# out8.net
KiCad netlist of a schematic drawn in EAGLE
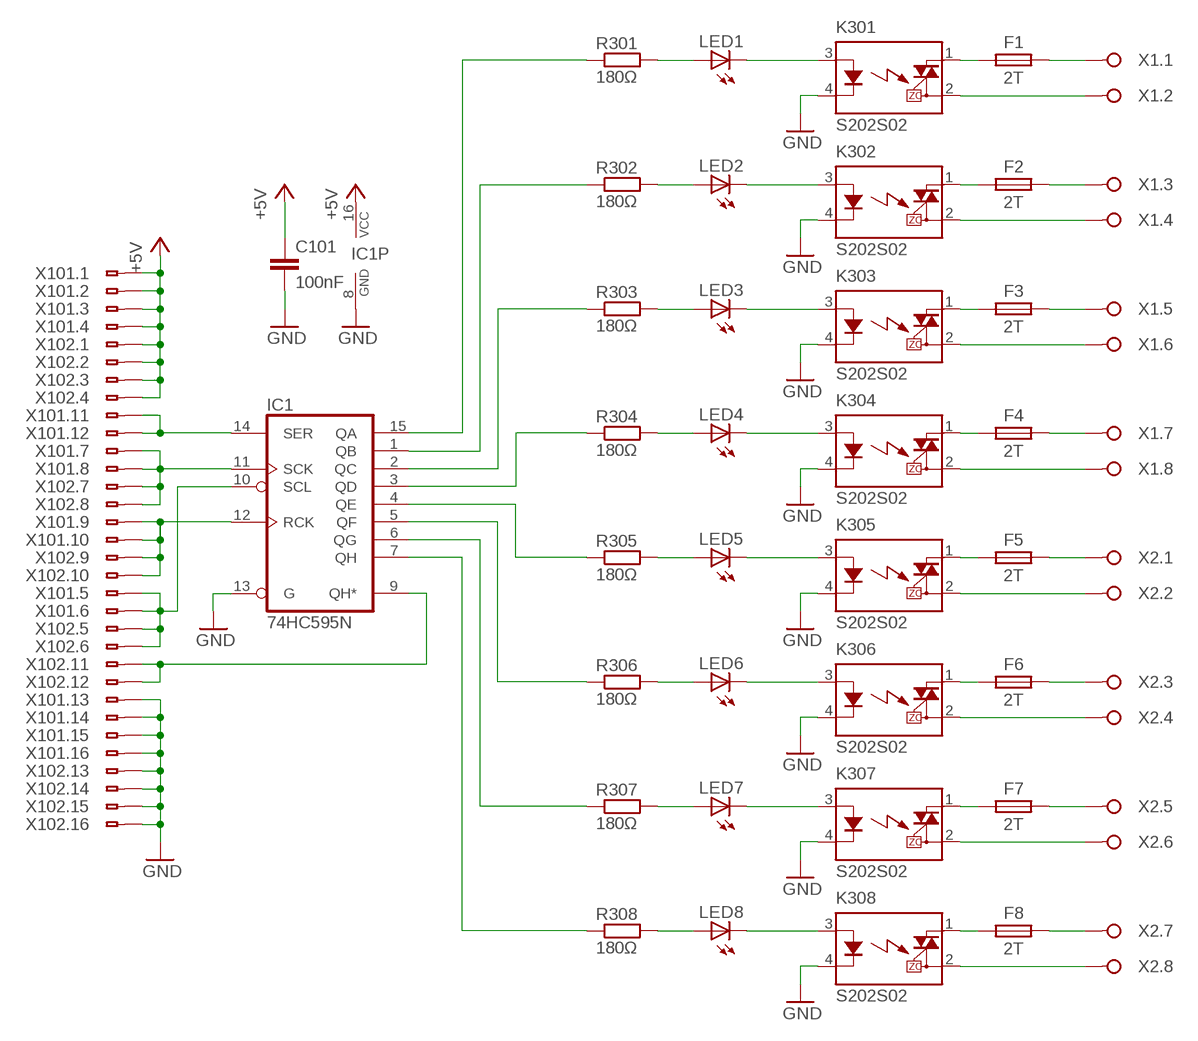
[diagram p0: schematic, sheet 1]

(export (version "E")
  (design (tool "Eeschema 10.0.6"))
  (components
    (comp (ref "C101")
      (value "100nF")
      (footprint "eagle-import:C025-025X050")
      (libsource (lib "eagle-import") (part "C_025-025X050"))
    )
    (comp (ref "F1")
      (value "2T")
      (footprint "eagle-import:TR5")
      (libsource (lib "eagle-import") (part "TR5"))
    )
    (comp (ref "F2")
      (value "2T")
      (footprint "eagle-import:TR5")
      (libsource (lib "eagle-import") (part "TR5"))
    )
    (comp (ref "F3")
      (value "2T")
      (footprint "eagle-import:TR5")
      (libsource (lib "eagle-import") (part "TR5"))
    )
    (comp (ref "F4")
      (value "2T")
      (footprint "eagle-import:TR5")
      (libsource (lib "eagle-import") (part "TR5"))
    )
    (comp (ref "F5")
      (value "2T")
      (footprint "eagle-import:TR5")
      (libsource (lib "eagle-import") (part "TR5"))
    )
    (comp (ref "F6")
      (value "2T")
      (footprint "eagle-import:TR5")
      (libsource (lib "eagle-import") (part "TR5"))
    )
    (comp (ref "F7")
      (value "2T")
      (footprint "eagle-import:TR5")
      (libsource (lib "eagle-import") (part "TR5"))
    )
    (comp (ref "F8")
      (value "2T")
      (footprint "eagle-import:TR5")
      (libsource (lib "eagle-import") (part "TR5"))
    )
    (comp (ref "IC1")
      (value "74HC595N")
      (footprint "eagle-import:DIL16")
      (libsource (lib "eagle-import") (part "74595NHC"))
    )
    (comp (ref "K301")
      (value "S202S02")
      (footprint "eagle-import:SIP4")
      (libsource (lib "eagle-import") (part "S02S022"))
    )
    (comp (ref "K302")
      (value "S202S02")
      (footprint "eagle-import:SIP4")
      (libsource (lib "eagle-import") (part "S02S022"))
    )
    (comp (ref "K303")
      (value "S202S02")
      (footprint "eagle-import:SIP4")
      (libsource (lib "eagle-import") (part "S02S022"))
    )
    (comp (ref "K304")
      (value "S202S02")
      (footprint "eagle-import:SIP4")
      (libsource (lib "eagle-import") (part "S02S022"))
    )
    (comp (ref "K305")
      (value "S202S02")
      (footprint "eagle-import:SIP4")
      (libsource (lib "eagle-import") (part "S02S022"))
    )
    (comp (ref "K306")
      (value "S202S02")
      (footprint "eagle-import:SIP4")
      (libsource (lib "eagle-import") (part "S02S022"))
    )
    (comp (ref "K307")
      (value "S202S02")
      (footprint "eagle-import:SIP4")
      (libsource (lib "eagle-import") (part "S02S022"))
    )
    (comp (ref "K308")
      (value "S202S02")
      (footprint "eagle-import:SIP4")
      (libsource (lib "eagle-import") (part "S02S022"))
    )
    (comp (ref "LED1")
      (value "LED3MM")
      (footprint "eagle-import:LED3MM")
      (libsource (lib "eagle-import") (part "LED3MM"))
    )
    (comp (ref "LED2")
      (value "LED3MM")
      (footprint "eagle-import:LED3MM")
      (libsource (lib "eagle-import") (part "LED3MM"))
    )
    (comp (ref "LED3")
      (value "LED3MM")
      (footprint "eagle-import:LED3MM")
      (libsource (lib "eagle-import") (part "LED3MM"))
    )
    (comp (ref "LED4")
      (value "LED3MM")
      (footprint "eagle-import:LED3MM")
      (libsource (lib "eagle-import") (part "LED3MM"))
    )
    (comp (ref "LED5")
      (value "LED3MM")
      (footprint "eagle-import:LED3MM")
      (libsource (lib "eagle-import") (part "LED3MM"))
    )
    (comp (ref "LED6")
      (value "LED3MM")
      (footprint "eagle-import:LED3MM")
      (libsource (lib "eagle-import") (part "LED3MM"))
    )
    (comp (ref "LED7")
      (value "LED3MM")
      (footprint "eagle-import:LED3MM")
      (libsource (lib "eagle-import") (part "LED3MM"))
    )
    (comp (ref "LED8")
      (value "LED3MM")
      (footprint "eagle-import:LED3MM")
      (libsource (lib "eagle-import") (part "LED3MM"))
    )
    (comp (ref "R301")
      (value "180Ω")
      (footprint "eagle-import:0204_7")
      (libsource (lib "eagle-import") (part "R_0204/7"))
    )
    (comp (ref "R302")
      (value "180Ω")
      (footprint "eagle-import:0204_7")
      (libsource (lib "eagle-import") (part "R_0204/7"))
    )
    (comp (ref "R303")
      (value "180Ω")
      (footprint "eagle-import:0204_7")
      (libsource (lib "eagle-import") (part "R_0204/7"))
    )
    (comp (ref "R304")
      (value "180Ω")
      (footprint "eagle-import:0204_7")
      (libsource (lib "eagle-import") (part "R_0204/7"))
    )
    (comp (ref "R305")
      (value "180Ω")
      (footprint "eagle-import:0204_7")
      (libsource (lib "eagle-import") (part "R_0204/7"))
    )
    (comp (ref "R306")
      (value "180Ω")
      (footprint "eagle-import:0204_7")
      (libsource (lib "eagle-import") (part "R_0204/7"))
    )
    (comp (ref "R307")
      (value "180Ω")
      (footprint "eagle-import:0204_7")
      (libsource (lib "eagle-import") (part "R_0204/7"))
    )
    (comp (ref "R308")
      (value "180Ω")
      (footprint "eagle-import:0204_7")
      (libsource (lib "eagle-import") (part "R_0204/7"))
    )
    (comp (ref "X1")
      (value "WAGO_236-408")
      (footprint "eagle-import:WAGO_236-408")
      (libsource (lib "eagle-import") (part "WAGO_236-408"))
    )
    (comp (ref "X2")
      (value "WAGO_236-408")
      (footprint "eagle-import:WAGO_236-408")
      (libsource (lib "eagle-import") (part "WAGO_236-408"))
    )
    (comp (ref "X101")
      (value "WS16V")
      (footprint "eagle-import:WS16V")
      (libsource (lib "eagle-import") (part "WS16V"))
    )
    (comp (ref "X102")
      (value "WS16V")
      (footprint "eagle-import:WS16V")
      (libsource (lib "eagle-import") (part "WS16V"))
    )
  )
  (nets
    (net (code "1") (name "+5V") (class "Default")
      (node (ref "C101") (pin "1") (pinfunction "1_1") (pintype "passive"))
      (node (ref "IC1") (pin "16") (pinfunction "VCC_16") (pintype "power_in"))
      (node (ref "X101") (pin "1") (pinfunction "A_1") (pintype "passive"))
      (node (ref "X101") (pin "2") (pinfunction "A_2") (pintype "passive"))
      (node (ref "X101") (pin "3") (pinfunction "A_3") (pintype "passive"))
      (node (ref "X101") (pin "4") (pinfunction "A_4") (pintype "passive"))
      (node (ref "X102") (pin "1") (pinfunction "A_1") (pintype "passive"))
      (node (ref "X102") (pin "2") (pinfunction "A_2") (pintype "passive"))
      (node (ref "X102") (pin "3") (pinfunction "A_3") (pintype "passive"))
      (node (ref "X102") (pin "4") (pinfunction "A_4") (pintype "passive"))
    )
    (net (code "2") (name "GND") (class "Default")
      (node (ref "C101") (pin "2") (pinfunction "2_2") (pintype "passive"))
      (node (ref "IC1") (pin "13") (pinfunction "G_13") (pintype "input"))
      (node (ref "IC1") (pin "8") (pinfunction "GND_8") (pintype "power_in"))
      (node (ref "K301") (pin "4") (pinfunction "K_4") (pintype "passive"))
      (node (ref "K302") (pin "4") (pinfunction "K_4") (pintype "passive"))
      (node (ref "K303") (pin "4") (pinfunction "K_4") (pintype "passive"))
      (node (ref "K304") (pin "4") (pinfunction "K_4") (pintype "passive"))
      (node (ref "K305") (pin "4") (pinfunction "K_4") (pintype "passive"))
      (node (ref "K306") (pin "4") (pinfunction "K_4") (pintype "passive"))
      (node (ref "K307") (pin "4") (pinfunction "K_4") (pintype "passive"))
      (node (ref "K308") (pin "4") (pinfunction "K_4") (pintype "passive"))
      (node (ref "X101") (pin "13") (pinfunction "A_13") (pintype "passive"))
      (node (ref "X101") (pin "14") (pinfunction "A_14") (pintype "passive"))
      (node (ref "X101") (pin "15") (pinfunction "A_15") (pintype "passive"))
      (node (ref "X101") (pin "16") (pinfunction "A_16") (pintype "passive"))
      (node (ref "X102") (pin "13") (pinfunction "A_13") (pintype "passive"))
      (node (ref "X102") (pin "14") (pinfunction "A_14") (pintype "passive"))
      (node (ref "X102") (pin "15") (pinfunction "A_15") (pintype "passive"))
      (node (ref "X102") (pin "16") (pinfunction "A_16") (pintype "passive"))
    )
    (net (code "3") (name "Net-(F1-Pad2)") (class "Default")
      (node (ref "F1") (pin "2") (pinfunction "2_2") (pintype "passive"))
      (node (ref "X1") (pin "A1") (pinfunction "A_A1") (pintype "passive"))
      (node (ref "X1") (pin "B1") (pinfunction "A_B1") (pintype "passive"))
    )
    (net (code "4") (name "Net-(F2-Pad2)") (class "Default")
      (node (ref "F2") (pin "2") (pinfunction "2_2") (pintype "passive"))
      (node (ref "X1") (pin "A3") (pinfunction "A_A3") (pintype "passive"))
      (node (ref "X1") (pin "B3") (pinfunction "A_B3") (pintype "passive"))
    )
    (net (code "5") (name "Net-(F3-Pad2)") (class "Default")
      (node (ref "F3") (pin "2") (pinfunction "2_2") (pintype "passive"))
      (node (ref "X1") (pin "A5") (pinfunction "A_A5") (pintype "passive"))
      (node (ref "X1") (pin "B5") (pinfunction "A_B5") (pintype "passive"))
    )
    (net (code "6") (name "Net-(F4-Pad2)") (class "Default")
      (node (ref "F4") (pin "2") (pinfunction "2_2") (pintype "passive"))
      (node (ref "X1") (pin "A7") (pinfunction "A_A7") (pintype "passive"))
      (node (ref "X1") (pin "B7") (pinfunction "A_B7") (pintype "passive"))
    )
    (net (code "7") (name "Net-(F5-Pad2)") (class "Default")
      (node (ref "F5") (pin "2") (pinfunction "2_2") (pintype "passive"))
      (node (ref "X2") (pin "A1") (pinfunction "A_A1") (pintype "passive"))
      (node (ref "X2") (pin "B1") (pinfunction "A_B1") (pintype "passive"))
    )
    (net (code "8") (name "Net-(F6-Pad2)") (class "Default")
      (node (ref "F6") (pin "2") (pinfunction "2_2") (pintype "passive"))
      (node (ref "X2") (pin "A3") (pinfunction "A_A3") (pintype "passive"))
      (node (ref "X2") (pin "B3") (pinfunction "A_B3") (pintype "passive"))
    )
    (net (code "9") (name "Net-(F7-Pad2)") (class "Default")
      (node (ref "F7") (pin "2") (pinfunction "2_2") (pintype "passive"))
      (node (ref "X2") (pin "A5") (pinfunction "A_A5") (pintype "passive"))
      (node (ref "X2") (pin "B5") (pinfunction "A_B5") (pintype "passive"))
    )
    (net (code "10") (name "Net-(F8-Pad2)") (class "Default")
      (node (ref "F8") (pin "2") (pinfunction "2_2") (pintype "passive"))
      (node (ref "X2") (pin "A7") (pinfunction "A_A7") (pintype "passive"))
      (node (ref "X2") (pin "B7") (pinfunction "A_B7") (pintype "passive"))
    )
    (net (code "11") (name "Net-(IC1A-QA)") (class "Default")
      (node (ref "IC1") (pin "15") (pinfunction "QA_15") (pintype "tri_state"))
      (node (ref "R301") (pin "1") (pinfunction "1_1") (pintype "passive"))
    )
    (net (code "12") (name "Net-(IC1A-QB)") (class "Default")
      (node (ref "IC1") (pin "1") (pinfunction "QB_1") (pintype "tri_state"))
      (node (ref "R302") (pin "1") (pinfunction "1_1") (pintype "passive"))
    )
    (net (code "13") (name "Net-(IC1A-QC)") (class "Default")
      (node (ref "IC1") (pin "2") (pinfunction "QC_2") (pintype "tri_state"))
      (node (ref "R303") (pin "1") (pinfunction "1_1") (pintype "passive"))
    )
    (net (code "14") (name "Net-(IC1A-QD)") (class "Default")
      (node (ref "IC1") (pin "3") (pinfunction "QD_3") (pintype "tri_state"))
      (node (ref "R304") (pin "1") (pinfunction "1_1") (pintype "passive"))
    )
    (net (code "15") (name "Net-(IC1A-QE)") (class "Default")
      (node (ref "IC1") (pin "4") (pinfunction "QE_4") (pintype "tri_state"))
      (node (ref "R305") (pin "1") (pinfunction "1_1") (pintype "passive"))
    )
    (net (code "16") (name "Net-(IC1A-QF)") (class "Default")
      (node (ref "IC1") (pin "5") (pinfunction "QF_5") (pintype "tri_state"))
      (node (ref "R306") (pin "1") (pinfunction "1_1") (pintype "passive"))
    )
    (net (code "17") (name "Net-(IC1A-QG)") (class "Default")
      (node (ref "IC1") (pin "6") (pinfunction "QG_6") (pintype "tri_state"))
      (node (ref "R307") (pin "1") (pinfunction "1_1") (pintype "passive"))
    )
    (net (code "18") (name "Net-(IC1A-QH)") (class "Default")
      (node (ref "IC1") (pin "7") (pinfunction "QH_7") (pintype "tri_state"))
      (node (ref "R308") (pin "1") (pinfunction "1_1") (pintype "passive"))
    )
    (net (code "19") (name "Net-(IC1A-QH*)") (class "Default")
      (node (ref "IC1") (pin "9") (pinfunction "QH*_9") (pintype "tri_state"))
      (node (ref "X102") (pin "11") (pinfunction "A_11") (pintype "passive"))
      (node (ref "X102") (pin "12") (pinfunction "A_12") (pintype "passive"))
    )
    (net (code "20") (name "Net-(IC1A-RCK)") (class "Default")
      (node (ref "IC1") (pin "12") (pinfunction "RCK_12") (pintype "input"))
      (node (ref "X101") (pin "10") (pinfunction "A_10") (pintype "passive"))
      (node (ref "X101") (pin "9") (pinfunction "A_9") (pintype "passive"))
      (node (ref "X102") (pin "10") (pinfunction "A_10") (pintype "passive"))
      (node (ref "X102") (pin "9") (pinfunction "A_9") (pintype "passive"))
    )
    (net (code "21") (name "Net-(IC1A-SCK)") (class "Default")
      (node (ref "IC1") (pin "11") (pinfunction "SCK_11") (pintype "input"))
      (node (ref "X101") (pin "7") (pinfunction "A_7") (pintype "passive"))
      (node (ref "X101") (pin "8") (pinfunction "A_8") (pintype "passive"))
      (node (ref "X102") (pin "7") (pinfunction "A_7") (pintype "passive"))
      (node (ref "X102") (pin "8") (pinfunction "A_8") (pintype "passive"))
    )
    (net (code "22") (name "Net-(IC1A-SCL)") (class "Default")
      (node (ref "IC1") (pin "10") (pinfunction "SCL_10") (pintype "input"))
      (node (ref "X101") (pin "5") (pinfunction "A_5") (pintype "passive"))
      (node (ref "X101") (pin "6") (pinfunction "A_6") (pintype "passive"))
      (node (ref "X102") (pin "5") (pinfunction "A_5") (pintype "passive"))
      (node (ref "X102") (pin "6") (pinfunction "A_6") (pintype "passive"))
    )
    (net (code "23") (name "Net-(IC1A-SER)") (class "Default")
      (node (ref "IC1") (pin "14") (pinfunction "SER_14") (pintype "input"))
      (node (ref "X101") (pin "11") (pinfunction "A_11") (pintype "passive"))
      (node (ref "X101") (pin "12") (pinfunction "A_12") (pintype "passive"))
    )
    (net (code "24") (name "Net-(K301-A)") (class "Default")
      (node (ref "K301") (pin "3") (pinfunction "A_3") (pintype "passive"))
      (node (ref "LED1") (pin "K") (pinfunction "C_K") (pintype "passive"))
    )
    (net (code "25") (name "Net-(K301-DS1)") (class "Default")
      (node (ref "F1") (pin "1") (pinfunction "1_1") (pintype "passive"))
      (node (ref "K301") (pin "1") (pinfunction "DS1_1") (pintype "passive"))
    )
    (net (code "26") (name "Net-(K301-DS2)") (class "Default")
      (node (ref "K301") (pin "2") (pinfunction "DS2_2") (pintype "passive"))
      (node (ref "X1") (pin "A2") (pinfunction "A_A2") (pintype "passive"))
      (node (ref "X1") (pin "B2") (pinfunction "A_B2") (pintype "passive"))
    )
    (net (code "27") (name "Net-(K302-A)") (class "Default")
      (node (ref "K302") (pin "3") (pinfunction "A_3") (pintype "passive"))
      (node (ref "LED2") (pin "K") (pinfunction "C_K") (pintype "passive"))
    )
    (net (code "28") (name "Net-(K302-DS1)") (class "Default")
      (node (ref "F2") (pin "1") (pinfunction "1_1") (pintype "passive"))
      (node (ref "K302") (pin "1") (pinfunction "DS1_1") (pintype "passive"))
    )
    (net (code "29") (name "Net-(K302-DS2)") (class "Default")
      (node (ref "K302") (pin "2") (pinfunction "DS2_2") (pintype "passive"))
      (node (ref "X1") (pin "A4") (pinfunction "A_A4") (pintype "passive"))
      (node (ref "X1") (pin "B4") (pinfunction "A_B4") (pintype "passive"))
    )
    (net (code "30") (name "Net-(K303-A)") (class "Default")
      (node (ref "K303") (pin "3") (pinfunction "A_3") (pintype "passive"))
      (node (ref "LED3") (pin "K") (pinfunction "C_K") (pintype "passive"))
    )
    (net (code "31") (name "Net-(K303-DS1)") (class "Default")
      (node (ref "F3") (pin "1") (pinfunction "1_1") (pintype "passive"))
      (node (ref "K303") (pin "1") (pinfunction "DS1_1") (pintype "passive"))
    )
    (net (code "32") (name "Net-(K303-DS2)") (class "Default")
      (node (ref "K303") (pin "2") (pinfunction "DS2_2") (pintype "passive"))
      (node (ref "X1") (pin "A6") (pinfunction "A_A6") (pintype "passive"))
      (node (ref "X1") (pin "B6") (pinfunction "A_B6") (pintype "passive"))
    )
    (net (code "33") (name "Net-(K304-A)") (class "Default")
      (node (ref "K304") (pin "3") (pinfunction "A_3") (pintype "passive"))
      (node (ref "LED4") (pin "K") (pinfunction "C_K") (pintype "passive"))
    )
    (net (code "34") (name "Net-(K304-DS1)") (class "Default")
      (node (ref "F4") (pin "1") (pinfunction "1_1") (pintype "passive"))
      (node (ref "K304") (pin "1") (pinfunction "DS1_1") (pintype "passive"))
    )
    (net (code "35") (name "Net-(K304-DS2)") (class "Default")
      (node (ref "K304") (pin "2") (pinfunction "DS2_2") (pintype "passive"))
      (node (ref "X1") (pin "A8") (pinfunction "A_A8") (pintype "passive"))
      (node (ref "X1") (pin "B8") (pinfunction "A_B8") (pintype "passive"))
    )
    (net (code "36") (name "Net-(K305-A)") (class "Default")
      (node (ref "K305") (pin "3") (pinfunction "A_3") (pintype "passive"))
      (node (ref "LED5") (pin "K") (pinfunction "C_K") (pintype "passive"))
    )
    (net (code "37") (name "Net-(K305-DS1)") (class "Default")
      (node (ref "F5") (pin "1") (pinfunction "1_1") (pintype "passive"))
      (node (ref "K305") (pin "1") (pinfunction "DS1_1") (pintype "passive"))
    )
    (net (code "38") (name "Net-(K305-DS2)") (class "Default")
      (node (ref "K305") (pin "2") (pinfunction "DS2_2") (pintype "passive"))
      (node (ref "X2") (pin "A2") (pinfunction "A_A2") (pintype "passive"))
      (node (ref "X2") (pin "B2") (pinfunction "A_B2") (pintype "passive"))
    )
    (net (code "39") (name "Net-(K306-A)") (class "Default")
      (node (ref "K306") (pin "3") (pinfunction "A_3") (pintype "passive"))
      (node (ref "LED6") (pin "K") (pinfunction "C_K") (pintype "passive"))
    )
    (net (code "40") (name "Net-(K306-DS1)") (class "Default")
      (node (ref "F6") (pin "1") (pinfunction "1_1") (pintype "passive"))
      (node (ref "K306") (pin "1") (pinfunction "DS1_1") (pintype "passive"))
    )
    (net (code "41") (name "Net-(K306-DS2)") (class "Default")
      (node (ref "K306") (pin "2") (pinfunction "DS2_2") (pintype "passive"))
      (node (ref "X2") (pin "A4") (pinfunction "A_A4") (pintype "passive"))
      (node (ref "X2") (pin "B4") (pinfunction "A_B4") (pintype "passive"))
    )
    (net (code "42") (name "Net-(K307-A)") (class "Default")
      (node (ref "K307") (pin "3") (pinfunction "A_3") (pintype "passive"))
      (node (ref "LED7") (pin "K") (pinfunction "C_K") (pintype "passive"))
    )
    (net (code "43") (name "Net-(K307-DS1)") (class "Default")
      (node (ref "F7") (pin "1") (pinfunction "1_1") (pintype "passive"))
      (node (ref "K307") (pin "1") (pinfunction "DS1_1") (pintype "passive"))
    )
    (net (code "44") (name "Net-(K307-DS2)") (class "Default")
      (node (ref "K307") (pin "2") (pinfunction "DS2_2") (pintype "passive"))
      (node (ref "X2") (pin "A6") (pinfunction "A_A6") (pintype "passive"))
      (node (ref "X2") (pin "B6") (pinfunction "A_B6") (pintype "passive"))
    )
    (net (code "45") (name "Net-(K308-A)") (class "Default")
      (node (ref "K308") (pin "3") (pinfunction "A_3") (pintype "passive"))
      (node (ref "LED8") (pin "K") (pinfunction "C_K") (pintype "passive"))
    )
    (net (code "46") (name "Net-(K308-DS1)") (class "Default")
      (node (ref "F8") (pin "1") (pinfunction "1_1") (pintype "passive"))
      (node (ref "K308") (pin "1") (pinfunction "DS1_1") (pintype "passive"))
    )
    (net (code "47") (name "Net-(K308-DS2)") (class "Default")
      (node (ref "K308") (pin "2") (pinfunction "DS2_2") (pintype "passive"))
      (node (ref "X2") (pin "A8") (pinfunction "A_A8") (pintype "passive"))
      (node (ref "X2") (pin "B8") (pinfunction "A_B8") (pintype "passive"))
    )
    (net (code "48") (name "Net-(LED1-PadA)") (class "Default")
      (node (ref "LED1") (pin "A") (pinfunction "A_A") (pintype "passive"))
      (node (ref "R301") (pin "2") (pinfunction "2_2") (pintype "passive"))
    )
    (net (code "49") (name "Net-(LED2-PadA)") (class "Default")
      (node (ref "LED2") (pin "A") (pinfunction "A_A") (pintype "passive"))
      (node (ref "R302") (pin "2") (pinfunction "2_2") (pintype "passive"))
    )
    (net (code "50") (name "Net-(LED3-PadA)") (class "Default")
      (node (ref "LED3") (pin "A") (pinfunction "A_A") (pintype "passive"))
      (node (ref "R303") (pin "2") (pinfunction "2_2") (pintype "passive"))
    )
    (net (code "51") (name "Net-(LED4-PadA)") (class "Default")
      (node (ref "LED4") (pin "A") (pinfunction "A_A") (pintype "passive"))
      (node (ref "R304") (pin "2") (pinfunction "2_2") (pintype "passive"))
    )
    (net (code "52") (name "Net-(LED5-PadA)") (class "Default")
      (node (ref "LED5") (pin "A") (pinfunction "A_A") (pintype "passive"))
      (node (ref "R305") (pin "2") (pinfunction "2_2") (pintype "passive"))
    )
    (net (code "53") (name "Net-(LED6-PadA)") (class "Default")
      (node (ref "LED6") (pin "A") (pinfunction "A_A") (pintype "passive"))
      (node (ref "R306") (pin "2") (pinfunction "2_2") (pintype "passive"))
    )
    (net (code "54") (name "Net-(LED7-PadA)") (class "Default")
      (node (ref "LED7") (pin "A") (pinfunction "A_A") (pintype "passive"))
      (node (ref "R307") (pin "2") (pinfunction "2_2") (pintype "passive"))
    )
    (net (code "55") (name "Net-(LED8-PadA)") (class "Default")
      (node (ref "LED8") (pin "A") (pinfunction "A_A") (pintype "passive"))
      (node (ref "R308") (pin "2") (pinfunction "2_2") (pintype "passive"))
    )
  )
)
